# ProPrj_AI-xiaozhi.net
KiCad netlist of a schematic drawn in EasyEDA Pro
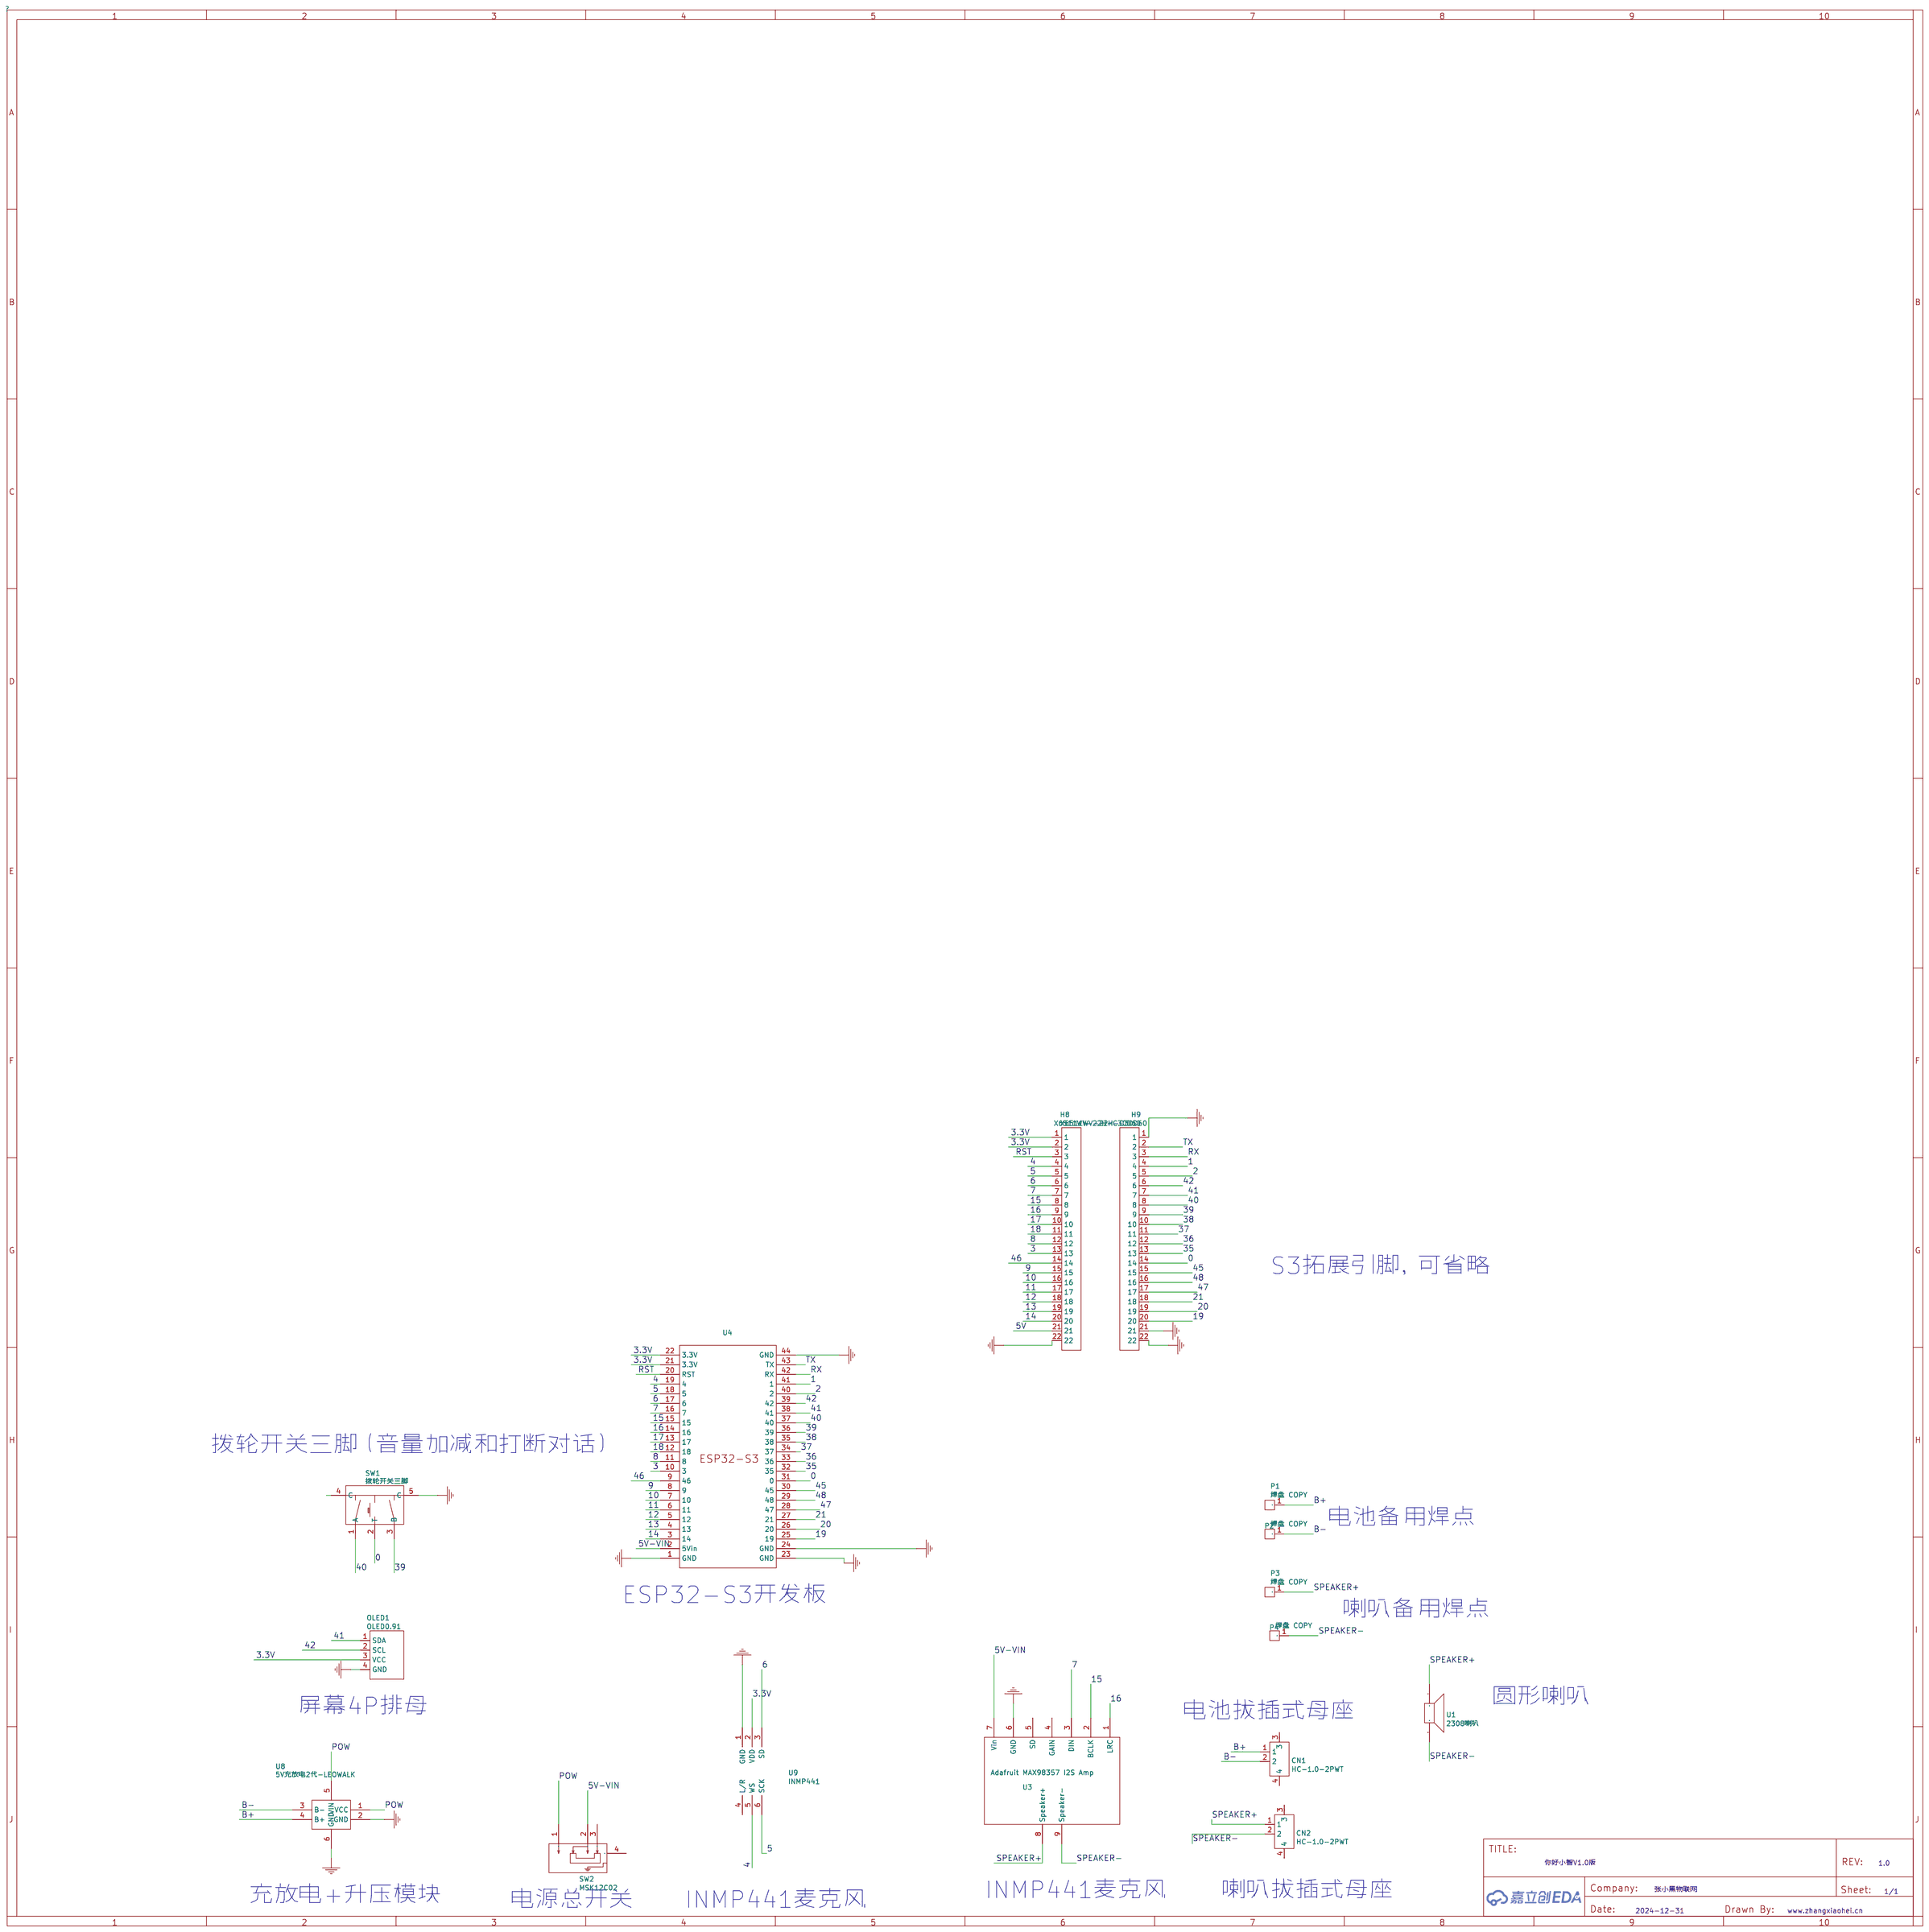
[diagram p0: schematic sheet]

(export (version "E")
  (design (tool "Eeschema 10.0.6"))
  (components
    (comp (ref "CN1")
      (value "HC-1.0-2PWT")
      (footprint "easyedapro:CONN-SMD_HC-1.0-2PWT")
      (fields (field (name "Manufacturer") "HCTL(华灿天禄)"))
      (libsource (lib "easyedapro") (part "HC-1.0-2PWT"))
    )
    (comp (ref "CN2")
      (value "HC-1.0-2PWT")
      (footprint "easyedapro:CONN-SMD_HC-1.0-2PWT")
      (fields (field (name "Manufacturer") "HCTL(华灿天禄)"))
      (libsource (lib "easyedapro") (part "HC-1.0-2PWT"))
    )
    (comp (ref "H8")
      (value "X6511WV-22H-C30D60")
      (footprint "easyedapro:HDR-TH_22P-P2.54-V-M")
      (fields
        (field (name "Manufacturer Part") "X6511WV-22H-C60D30")
        (field (name "Manufacturer") "XKB Connection(中国星坤)")
      )
      (libsource (lib "easyedapro") (part "X6511WV-22H-C30D60"))
    )
    (comp (ref "H9")
      (value "X6511WV-22H-C30D60")
      (footprint "easyedapro:HDR-TH_22P-P2.54-V-M")
      (fields
        (field (name "Manufacturer Part") "X6511WV-22H-C60D30")
        (field (name "Manufacturer") "XKB Connection(中国星坤)")
      )
      (libsource (lib "") (part "X6511WV-22H-C30D60_1"))
    )
    (comp (ref "OLED1") (value "OLED0.91") (libsource (lib "easyedapro") (part "OLED0.91")))
    (comp (ref "P1") (value "焊盘 COPY") (libsource (lib "easyedapro") (part "焊盘 COPY")))
    (comp (ref "P2") (value "焊盘 COPY") (libsource (lib "easyedapro") (part "焊盘 COPY")))
    (comp (ref "P3") (value "焊盘 COPY") (libsource (lib "easyedapro") (part "焊盘 COPY")))
    (comp (ref "P4") (value "焊盘 COPY") (libsource (lib "easyedapro") (part "焊盘 COPY")))
    (comp (ref "SW1") (value "拨轮开关三脚") (libsource (lib "easyedapro") (part "拨轮开关三脚")))
    (comp (ref "SW2")
      (value "MSK12C02")
      (footprint "easyedapro:SW-TH_MSK12C02")
      (fields (field (name "Manufacturer") "SHOU HAN(首韩)"))
      (libsource (lib "easyedapro") (part "MSK12C02"))
    )
    (comp (ref "U1")
      (value "2308喇叭")
      (fields (field (name "Manufacturer Part") "喇叭"))
      (libsource (lib "easyedapro") (part "2308喇叭"))
    )
    (comp (ref "U3")
      (value "Adafruit MAX98357 I2S Amp")
      (libsource (lib "easyedapro") (part "Adafruit MAX98357 I2S Amp"))
    )
    (comp (ref "U4") (value "NO") (libsource (lib "easyedapro") (part "NO")))
    (comp (ref "U8")
      (value "5V充放电2代-LEOWALK")
      (fields (field (name "Manufacturer Part") "TJC3224K028_011") (field (name "Manufacturer") "TJC"))
      (libsource (lib "easyedapro") (part "5V充放电2代-LEOWALK"))
    )
    (comp (ref "U9") (value "INMP441") (libsource (lib "easyedapro") (part "INMP441")))
  )
  (nets
    (net (code "1") (name "/0") (class "Default")
      (node (ref "H9") (pin "14") (pinfunction "14_14") (pintype "unspecified"))
      (node (ref "SW1") (pin "2") (pinfunction "T_2") (pintype "unspecified"))
      (node (ref "U4") (pin "31") (pinfunction "0_31") (pintype "unspecified"))
    )
    (net (code "2") (name "/1") (class "Default")
      (node (ref "H9") (pin "4") (pinfunction "4_4") (pintype "unspecified"))
      (node (ref "U4") (pin "41") (pinfunction "1_41") (pintype "unspecified"))
    )
    (net (code "3") (name "/2") (class "Default")
      (node (ref "H9") (pin "5") (pinfunction "5_5") (pintype "unspecified"))
      (node (ref "U4") (pin "40") (pinfunction "2_40") (pintype "unspecified"))
    )
    (net (code "4") (name "/3") (class "Default")
      (node (ref "H8") (pin "13") (pinfunction "13_13") (pintype "unspecified"))
      (node (ref "U4") (pin "10") (pinfunction "3_10") (pintype "unspecified"))
    )
    (net (code "5") (name "/3.3V") (class "Default")
      (node (ref "H8") (pin "1") (pinfunction "1_1") (pintype "unspecified"))
      (node (ref "H8") (pin "2") (pinfunction "2_2") (pintype "unspecified"))
      (node (ref "OLED1") (pin "3") (pinfunction "VCC_3") (pintype "input"))
      (node (ref "U4") (pin "21") (pinfunction "3.3V_21") (pintype "unspecified"))
      (node (ref "U4") (pin "22") (pinfunction "3.3V_22") (pintype "unspecified"))
      (node (ref "U9") (pin "2") (pinfunction "VDD_2") (pintype "unspecified"))
    )
    (net (code "6") (name "/4") (class "Default")
      (node (ref "H8") (pin "4") (pinfunction "4_4") (pintype "unspecified"))
      (node (ref "U4") (pin "19") (pinfunction "4_19") (pintype "unspecified"))
      (node (ref "U9") (pin "5") (pinfunction "WS_5") (pintype "unspecified"))
    )
    (net (code "7") (name "/5") (class "Default")
      (node (ref "H8") (pin "5") (pinfunction "5_5") (pintype "unspecified"))
      (node (ref "U4") (pin "18") (pinfunction "5_18") (pintype "unspecified"))
      (node (ref "U9") (pin "6") (pinfunction "SCK_6") (pintype "unspecified"))
    )
    (net (code "8") (name "/5V") (class "Default")
      (node (ref "H8") (pin "21") (pinfunction "21_21") (pintype "unspecified"))
    )
    (net (code "9") (name "/5V-VIN") (class "Default")
      (node (ref "SW2") (pin "2") (pinfunction "2_2") (pintype "unspecified"))
      (node (ref "U3") (pin "7") (pinfunction "Vin_7") (pintype "unspecified"))
      (node (ref "U4") (pin "2") (pinfunction "5Vin_2") (pintype "unspecified"))
    )
    (net (code "10") (name "/6") (class "Default")
      (node (ref "H8") (pin "6") (pinfunction "6_6") (pintype "unspecified"))
      (node (ref "U4") (pin "17") (pinfunction "6_17") (pintype "unspecified"))
      (node (ref "U9") (pin "3") (pinfunction "SD_3") (pintype "unspecified"))
    )
    (net (code "11") (name "/7") (class "Default")
      (node (ref "H8") (pin "7") (pinfunction "7_7") (pintype "unspecified"))
      (node (ref "U3") (pin "3") (pinfunction "DIN_3") (pintype "unspecified"))
      (node (ref "U4") (pin "16") (pinfunction "7_16") (pintype "unspecified"))
    )
    (net (code "12") (name "/8") (class "Default")
      (node (ref "H8") (pin "12") (pinfunction "12_12") (pintype "unspecified"))
      (node (ref "U4") (pin "11") (pinfunction "8_11") (pintype "unspecified"))
    )
    (net (code "13") (name "/9") (class "Default")
      (node (ref "H8") (pin "15") (pinfunction "15_15") (pintype "unspecified"))
      (node (ref "U4") (pin "8") (pinfunction "9_8") (pintype "unspecified"))
    )
    (net (code "14") (name "/10") (class "Default")
      (node (ref "H8") (pin "16") (pinfunction "16_16") (pintype "unspecified"))
      (node (ref "U4") (pin "7") (pinfunction "10_7") (pintype "unspecified"))
    )
    (net (code "15") (name "/11") (class "Default")
      (node (ref "H8") (pin "17") (pinfunction "17_17") (pintype "unspecified"))
      (node (ref "U4") (pin "6") (pinfunction "11_6") (pintype "unspecified"))
    )
    (net (code "16") (name "/12") (class "Default")
      (node (ref "H8") (pin "18") (pinfunction "18_18") (pintype "unspecified"))
      (node (ref "U4") (pin "5") (pinfunction "12_5") (pintype "unspecified"))
    )
    (net (code "17") (name "/13") (class "Default")
      (node (ref "H8") (pin "19") (pinfunction "19_19") (pintype "unspecified"))
      (node (ref "U4") (pin "4") (pinfunction "13_4") (pintype "unspecified"))
    )
    (net (code "18") (name "/14") (class "Default")
      (node (ref "H8") (pin "20") (pinfunction "20_20") (pintype "unspecified"))
      (node (ref "U4") (pin "3") (pinfunction "14_3") (pintype "unspecified"))
    )
    (net (code "19") (name "/15") (class "Default")
      (node (ref "H8") (pin "8") (pinfunction "8_8") (pintype "unspecified"))
      (node (ref "U3") (pin "2") (pinfunction "BCLK_2") (pintype "unspecified"))
      (node (ref "U4") (pin "15") (pinfunction "15_15") (pintype "unspecified"))
    )
    (net (code "20") (name "/16") (class "Default")
      (node (ref "H8") (pin "9") (pinfunction "9_9") (pintype "unspecified"))
      (node (ref "U3") (pin "1") (pinfunction "LRC_1") (pintype "unspecified"))
      (node (ref "U4") (pin "14") (pinfunction "16_14") (pintype "unspecified"))
    )
    (net (code "21") (name "/17") (class "Default")
      (node (ref "H8") (pin "10") (pinfunction "10_10") (pintype "unspecified"))
      (node (ref "U4") (pin "13") (pinfunction "17_13") (pintype "unspecified"))
    )
    (net (code "22") (name "/18") (class "Default")
      (node (ref "H8") (pin "11") (pinfunction "11_11") (pintype "unspecified"))
      (node (ref "U4") (pin "12") (pinfunction "18_12") (pintype "unspecified"))
    )
    (net (code "23") (name "/19") (class "Default")
      (node (ref "H9") (pin "20") (pinfunction "20_20") (pintype "unspecified"))
      (node (ref "U4") (pin "25") (pinfunction "19_25") (pintype "unspecified"))
    )
    (net (code "24") (name "/20") (class "Default")
      (node (ref "H9") (pin "19") (pinfunction "19_19") (pintype "unspecified"))
      (node (ref "U4") (pin "26") (pinfunction "20_26") (pintype "unspecified"))
    )
    (net (code "25") (name "/21") (class "Default")
      (node (ref "H9") (pin "18") (pinfunction "18_18") (pintype "unspecified"))
      (node (ref "U4") (pin "27") (pinfunction "21_27") (pintype "unspecified"))
    )
    (net (code "26") (name "/35") (class "Default")
      (node (ref "H9") (pin "13") (pinfunction "13_13") (pintype "unspecified"))
      (node (ref "U4") (pin "32") (pinfunction "35_32") (pintype "unspecified"))
    )
    (net (code "27") (name "/36") (class "Default")
      (node (ref "H9") (pin "12") (pinfunction "12_12") (pintype "unspecified"))
      (node (ref "U4") (pin "33") (pinfunction "36_33") (pintype "unspecified"))
    )
    (net (code "28") (name "/37") (class "Default")
      (node (ref "H9") (pin "11") (pinfunction "11_11") (pintype "unspecified"))
      (node (ref "U4") (pin "34") (pinfunction "37_34") (pintype "unspecified"))
    )
    (net (code "29") (name "/38") (class "Default")
      (node (ref "H9") (pin "10") (pinfunction "10_10") (pintype "unspecified"))
      (node (ref "U4") (pin "35") (pinfunction "38_35") (pintype "unspecified"))
    )
    (net (code "30") (name "/39") (class "Default")
      (node (ref "H9") (pin "9") (pinfunction "9_9") (pintype "unspecified"))
      (node (ref "SW1") (pin "3") (pinfunction "B_3") (pintype "unspecified"))
      (node (ref "U4") (pin "36") (pinfunction "39_36") (pintype "unspecified"))
    )
    (net (code "31") (name "/40") (class "Default")
      (node (ref "H9") (pin "8") (pinfunction "8_8") (pintype "unspecified"))
      (node (ref "SW1") (pin "1") (pinfunction "A_1") (pintype "unspecified"))
      (node (ref "U4") (pin "37") (pinfunction "40_37") (pintype "unspecified"))
    )
    (net (code "32") (name "/41") (class "Default")
      (node (ref "H9") (pin "7") (pinfunction "7_7") (pintype "unspecified"))
      (node (ref "OLED1") (pin "1") (pinfunction "SDA_1") (pintype "input"))
      (node (ref "U4") (pin "38") (pinfunction "41_38") (pintype "unspecified"))
    )
    (net (code "33") (name "/42") (class "Default")
      (node (ref "H9") (pin "6") (pinfunction "6_6") (pintype "unspecified"))
      (node (ref "OLED1") (pin "2") (pinfunction "SCL_2") (pintype "input"))
      (node (ref "U4") (pin "39") (pinfunction "42_39") (pintype "unspecified"))
    )
    (net (code "34") (name "/45") (class "Default")
      (node (ref "H9") (pin "15") (pinfunction "15_15") (pintype "unspecified"))
      (node (ref "U4") (pin "30") (pinfunction "45_30") (pintype "unspecified"))
    )
    (net (code "35") (name "/46") (class "Default")
      (node (ref "H8") (pin "14") (pinfunction "14_14") (pintype "unspecified"))
      (node (ref "U4") (pin "9") (pinfunction "46_9") (pintype "unspecified"))
    )
    (net (code "36") (name "/47") (class "Default")
      (node (ref "H9") (pin "17") (pinfunction "17_17") (pintype "unspecified"))
      (node (ref "U4") (pin "28") (pinfunction "47_28") (pintype "unspecified"))
    )
    (net (code "37") (name "/48") (class "Default")
      (node (ref "H9") (pin "16") (pinfunction "16_16") (pintype "unspecified"))
      (node (ref "U4") (pin "29") (pinfunction "48_29") (pintype "unspecified"))
    )
    (net (code "38") (name "/B+") (class "Default")
      (node (ref "CN1") (pin "1") (pinfunction "1_1") (pintype "unspecified"))
      (node (ref "P1") (pin "1") (pinfunction "1_1") (pintype "unspecified"))
      (node (ref "U8") (pin "4") (pinfunction "B+_4") (pintype "unspecified"))
    )
    (net (code "39") (name "/B-") (class "Default")
      (node (ref "CN1") (pin "2") (pinfunction "2_2") (pintype "unspecified"))
      (node (ref "P2") (pin "1") (pinfunction "1_1") (pintype "unspecified"))
      (node (ref "U8") (pin "3") (pinfunction "B-_3") (pintype "unspecified"))
    )
    (net (code "40") (name "/POW") (class "Default")
      (node (ref "SW2") (pin "1") (pinfunction "1_1") (pintype "unspecified"))
      (node (ref "U8") (pin "1") (pinfunction "VCC_1") (pintype "unspecified"))
      (node (ref "U8") (pin "5") (pinfunction "VIN_5") (pintype "unspecified"))
    )
    (net (code "41") (name "/RST") (class "Default")
      (node (ref "H8") (pin "3") (pinfunction "3_3") (pintype "unspecified"))
      (node (ref "U4") (pin "20") (pinfunction "RST_20") (pintype "unspecified"))
    )
    (net (code "42") (name "/RX") (class "Default")
      (node (ref "H9") (pin "3") (pinfunction "3_3") (pintype "unspecified"))
      (node (ref "U4") (pin "42") (pinfunction "RX_42") (pintype "unspecified"))
    )
    (net (code "43") (name "/SPEAKER+") (class "Default")
      (node (ref "CN2") (pin "1") (pinfunction "1_1") (pintype "unspecified"))
      (node (ref "P3") (pin "1") (pinfunction "1_1") (pintype "unspecified"))
      (node (ref "U1") (pin "1") (pinfunction "1_1") (pintype "unspecified"))
      (node (ref "U3") (pin "8") (pinfunction "Speaker+_8") (pintype "unspecified"))
    )
    (net (code "44") (name "/SPEAKER-") (class "Default")
      (node (ref "CN2") (pin "2") (pinfunction "2_2") (pintype "unspecified"))
      (node (ref "P4") (pin "1") (pinfunction "1_1") (pintype "unspecified"))
      (node (ref "U1") (pin "2") (pinfunction "2_2") (pintype "unspecified"))
      (node (ref "U3") (pin "9") (pinfunction "Speaker-_9") (pintype "unspecified"))
    )
    (net (code "45") (name "/TX") (class "Default")
      (node (ref "H9") (pin "2") (pinfunction "2_2") (pintype "unspecified"))
      (node (ref "U4") (pin "43") (pinfunction "TX_43") (pintype "unspecified"))
    )
    (net (code "46") (name "GND") (class "Default")
      (node (ref "H8") (pin "22") (pinfunction "22_22") (pintype "unspecified"))
      (node (ref "H9") (pin "1") (pinfunction "1_1") (pintype "unspecified"))
      (node (ref "H9") (pin "21") (pinfunction "21_21") (pintype "unspecified"))
      (node (ref "H9") (pin "22") (pinfunction "22_22") (pintype "unspecified"))
      (node (ref "OLED1") (pin "4") (pinfunction "GND_4") (pintype "input"))
      (node (ref "SW1") (pin "5") (pinfunction "C_5") (pintype "unspecified"))
      (node (ref "U3") (pin "6") (pinfunction "GND_6") (pintype "unspecified"))
      (node (ref "U4") (pin "1") (pinfunction "GND_1") (pintype "unspecified"))
      (node (ref "U4") (pin "23") (pinfunction "GND_23") (pintype "unspecified"))
      (node (ref "U4") (pin "24") (pinfunction "GND_24") (pintype "unspecified"))
      (node (ref "U4") (pin "44") (pinfunction "GND_44") (pintype "unspecified"))
      (node (ref "U8") (pin "2") (pinfunction "GND_2") (pintype "unspecified"))
      (node (ref "U8") (pin "6") (pinfunction "GND_6") (pintype "unspecified"))
      (node (ref "U9") (pin "1") (pinfunction "GND_1") (pintype "unspecified"))
    )
    (net (code "47") (name "unconnected-(CN1-Pad3)") (class "Default")
      (node (ref "CN1") (pin "3") (pinfunction "3_3") (pintype "unspecified"))
    )
    (net (code "48") (name "unconnected-(CN1-Pad4)") (class "Default")
      (node (ref "CN1") (pin "4") (pinfunction "4_4") (pintype "unspecified"))
    )
    (net (code "49") (name "unconnected-(CN2-Pad3)") (class "Default")
      (node (ref "CN2") (pin "3") (pinfunction "3_3") (pintype "unspecified"))
    )
    (net (code "50") (name "unconnected-(CN2-Pad4)") (class "Default")
      (node (ref "CN2") (pin "4") (pinfunction "4_4") (pintype "unspecified"))
    )
    (net (code "51") (name "unconnected-(SW1-C-Pad4)") (class "Default")
      (node (ref "SW1") (pin "4") (pinfunction "C_4") (pintype "unspecified"))
    )
    (net (code "52") (name "unconnected-(SW2-Pad3)") (class "Default")
      (node (ref "SW2") (pin "3") (pinfunction "3_3") (pintype "unspecified"))
    )
    (net (code "53") (name "unconnected-(SW2-Pad4)") (class "Default")
      (node (ref "SW2") (pin "4") (pinfunction "4_4") (pintype "unspecified"))
    )
    (net (code "54") (name "unconnected-(U3-GAIN-Pad4)") (class "Default")
      (node (ref "U3") (pin "4") (pinfunction "GAIN_4") (pintype "unspecified"))
    )
    (net (code "55") (name "unconnected-(U3-SD-Pad5)") (class "Default")
      (node (ref "U3") (pin "5") (pinfunction "SD_5") (pintype "unspecified"))
    )
    (net (code "56") (name "unconnected-(U9-L{slash}R-Pad4)") (class "Default")
      (node (ref "U9") (pin "4") (pinfunction "L/R_4") (pintype "unspecified"))
    )
  )
)
